# esp32s3_min_system.net
KiCad netlist of a schematic drawn in EasyEDA Pro
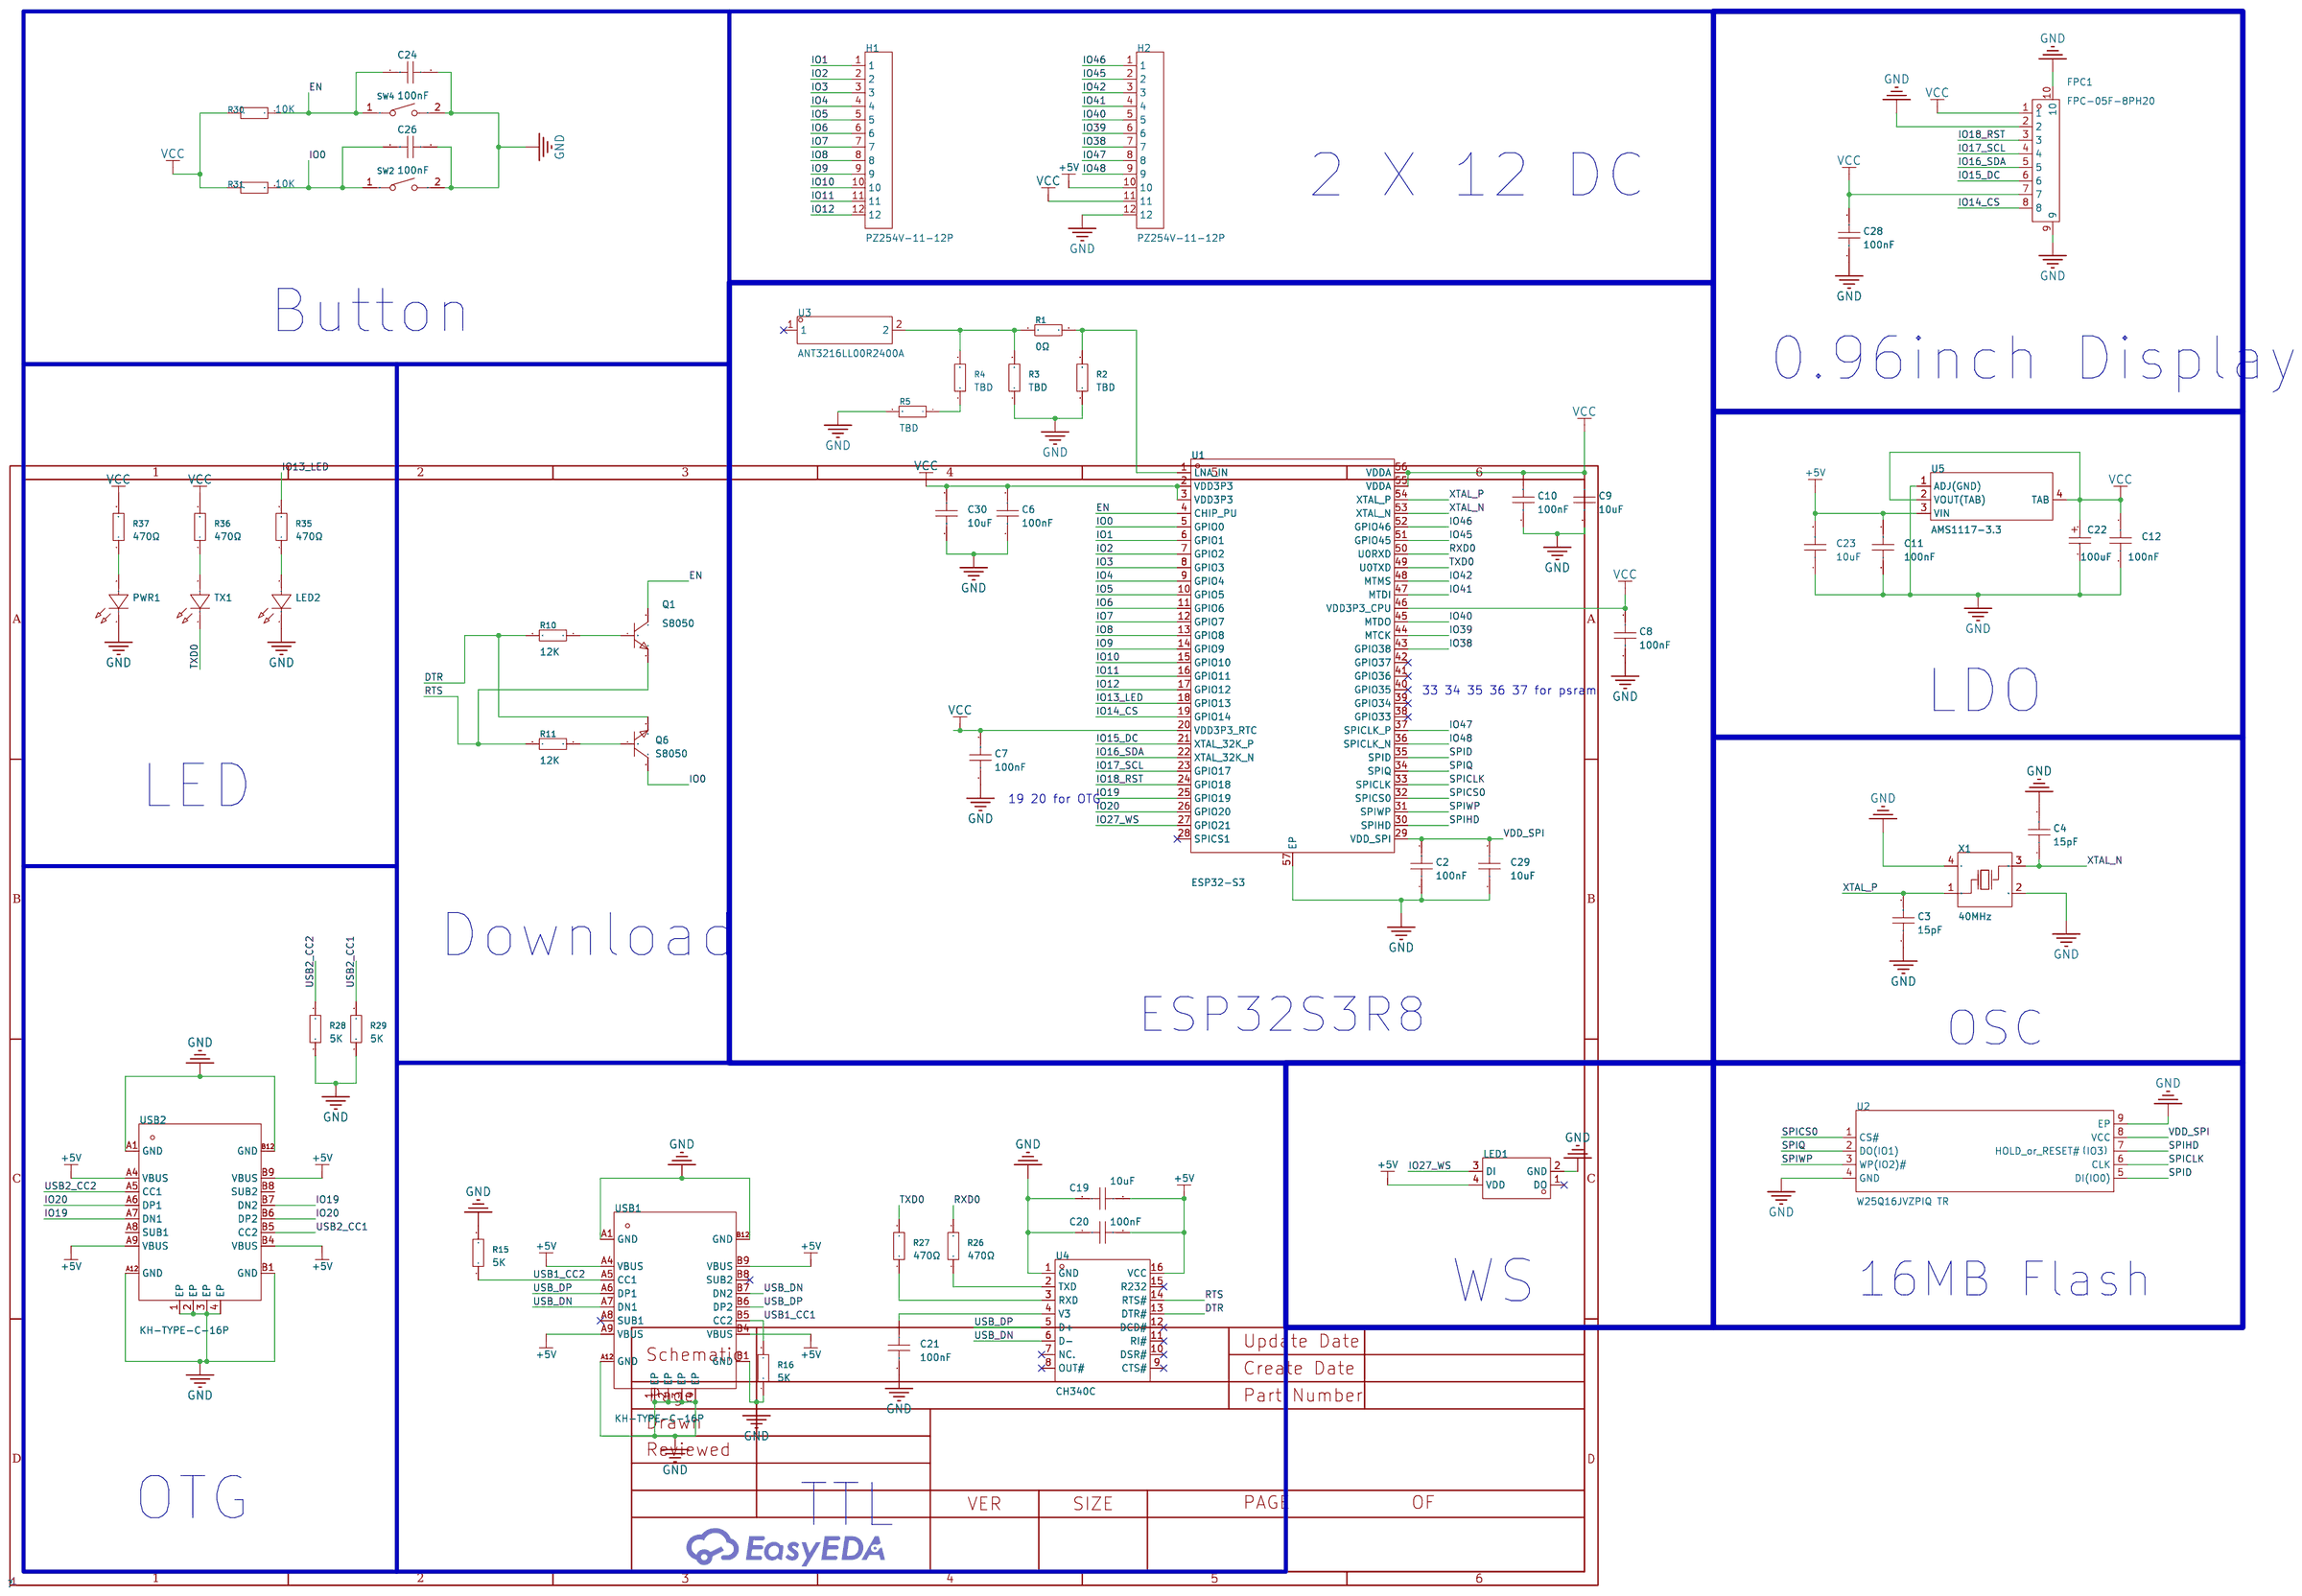
[diagram p0: schematic sheet]

(export (version "E")
  (design (tool "Eeschema 10.0.6"))
  (components
    (comp (ref "C2")
      (value "100nF")
      (footprint "easyedapro:C0402")
      (fields
        (field (name "Manufacturer Part") "CL05A105KA5NQNC")
        (field (name "Manufacturer") "SAMSUNG(三星)")
      )
      (libsource (lib "easyedapro") (part "CL05A105KA5NQNC"))
    )
    (comp (ref "C3")
      (value "15pF")
      (footprint "easyedapro:C0402")
      (fields
        (field (name "Manufacturer Part") "CL05A105KA5NQNC")
        (field (name "Manufacturer") "SAMSUNG(三星)")
      )
      (libsource (lib "easyedapro") (part "CL05A105KA5NQNC"))
    )
    (comp (ref "C4")
      (value "15pF")
      (footprint "easyedapro:C0402")
      (fields
        (field (name "Manufacturer Part") "CL05A105KA5NQNC")
        (field (name "Manufacturer") "SAMSUNG(三星)")
      )
      (libsource (lib "easyedapro") (part "CL05A105KA5NQNC"))
    )
    (comp (ref "C6")
      (value "100nF")
      (footprint "easyedapro:C0402")
      (fields
        (field (name "Manufacturer Part") "CL05A105KA5NQNC")
        (field (name "Manufacturer") "SAMSUNG(三星)")
      )
      (libsource (lib "easyedapro") (part "CL05A105KA5NQNC"))
    )
    (comp (ref "C7")
      (value "100nF")
      (footprint "easyedapro:C0402")
      (fields
        (field (name "Manufacturer Part") "CL05A105KA5NQNC")
        (field (name "Manufacturer") "SAMSUNG(三星)")
      )
      (libsource (lib "easyedapro") (part "CL05A105KA5NQNC"))
    )
    (comp (ref "C8")
      (value "100nF")
      (footprint "easyedapro:C0402")
      (fields
        (field (name "Manufacturer Part") "CL05A105KA5NQNC")
        (field (name "Manufacturer") "SAMSUNG(三星)")
      )
      (libsource (lib "easyedapro") (part "CL05A105KA5NQNC"))
    )
    (comp (ref "C9")
      (value "10uF")
      (footprint "easyedapro:C0402")
      (fields
        (field (name "Manufacturer Part") "CL05A105KA5NQNC")
        (field (name "Manufacturer") "SAMSUNG(三星)")
      )
      (libsource (lib "easyedapro") (part "CL05A105KA5NQNC"))
    )
    (comp (ref "C10")
      (value "100nF")
      (footprint "easyedapro:C0402")
      (fields
        (field (name "Manufacturer Part") "CL05A105KA5NQNC")
        (field (name "Manufacturer") "SAMSUNG(三星)")
      )
      (libsource (lib "easyedapro") (part "CL05A105KA5NQNC"))
    )
    (comp (ref "C11")
      (value "100nF")
      (footprint "easyedapro:C0402")
      (fields
        (field (name "Manufacturer Part") "CL05B104KO5NNNC")
        (field (name "Manufacturer") "SAMSUNG(三星)")
      )
      (libsource (lib "easyedapro") (part "CL05B104KO5NNNC"))
    )
    (comp (ref "C12")
      (value "100nF")
      (footprint "easyedapro:C0402")
      (fields
        (field (name "Manufacturer Part") "CL05B104KO5NNNC")
        (field (name "Manufacturer") "SAMSUNG(三星)")
      )
      (libsource (lib "easyedapro") (part "CL05B104KO5NNNC"))
    )
    (comp (ref "C19")
      (value "10uF")
      (footprint "easyedapro:C0603")
      (description "Capacitance:10uF Tolerance:±10% Tolerance:±10% Voltage Rating:10V Temperature Coefficient:X5R")
      (fields
        (field (name "Manufacturer Part") "CGA0603X5R106K100JT")
        (field (name "Manufacturer") "HRE(芯声)")
      )
      (libsource (lib "easyedapro") (part "CGA0603X5R106K100JT"))
    )
    (comp (ref "C20")
      (value "100nF")
      (footprint "easyedapro:C0402")
      (fields
        (field (name "Manufacturer Part") "CL05B104KO5NNNC")
        (field (name "Manufacturer") "SAMSUNG(三星)")
      )
      (libsource (lib "easyedapro") (part "CL05B104KO5NNNC"))
    )
    (comp (ref "C21")
      (value "100nF")
      (footprint "easyedapro:C0402")
      (fields
        (field (name "Manufacturer Part") "CL05B104KO5NNNC")
        (field (name "Manufacturer") "SAMSUNG(三星)")
      )
      (libsource (lib "easyedapro") (part "CL05B104KO5NNNC"))
    )
    (comp (ref "C22")
      (value "100uF")
      (footprint "easyedapro:CASE-B_3528")
      (fields (field (name "Manufacturer Part") "TAJB107K006RNJ") (field (name "Manufacturer") "Kyocera AVX"))
      (libsource (lib "easyedapro") (part "TAJB107K006RNJ"))
    )
    (comp (ref "C23")
      (value "10uF")
      (footprint "easyedapro:C0603")
      (description "Capacitance:10uF Tolerance:±10% Tolerance:±10% Voltage Rating:10V Temperature Coefficient:X5R")
      (fields
        (field (name "Manufacturer Part") "CGA0603X5R106K100JT")
        (field (name "Manufacturer") "HRE(芯声)")
      )
      (libsource (lib "easyedapro") (part "CGA0603X5R106K100JT"))
    )
    (comp (ref "C24")
      (value "100nF")
      (footprint "easyedapro:C0402")
      (fields
        (field (name "Manufacturer Part") "CL05B104KO5NNNC")
        (field (name "Manufacturer") "SAMSUNG(三星)")
      )
      (libsource (lib "easyedapro") (part "CL05B104KO5NNNC"))
    )
    (comp (ref "C26")
      (value "100nF")
      (footprint "easyedapro:C0402")
      (fields
        (field (name "Manufacturer Part") "CL05B104KO5NNNC")
        (field (name "Manufacturer") "SAMSUNG(三星)")
      )
      (libsource (lib "easyedapro") (part "CL05B104KO5NNNC"))
    )
    (comp (ref "C28")
      (value "100nF")
      (footprint "easyedapro:C0402")
      (fields
        (field (name "Manufacturer Part") "CL05A105KA5NQNC")
        (field (name "Manufacturer") "SAMSUNG(三星)")
      )
      (libsource (lib "easyedapro") (part "CL05A105KA5NQNC"))
    )
    (comp (ref "C29")
      (value "10uF")
      (footprint "easyedapro:C0603")
      (description "Capacitance:10uF Tolerance:±10% Tolerance:±10% Voltage Rating:10V Temperature Coefficient:X5R")
      (fields
        (field (name "Manufacturer Part") "CGA0603X5R106K100JT")
        (field (name "Manufacturer") "HRE(芯声)")
      )
      (libsource (lib "easyedapro") (part "CGA0603X5R106K100JT"))
    )
    (comp (ref "C30")
      (value "10uF")
      (footprint "easyedapro:C0603")
      (description "Capacitance:10uF Tolerance:±10% Tolerance:±10% Voltage Rating:10V Temperature Coefficient:X5R")
      (fields
        (field (name "Manufacturer Part") "CGA0603X5R106K100JT")
        (field (name "Manufacturer") "HRE(芯声)")
      )
      (libsource (lib "easyedapro") (part "CGA0603X5R106K100JT"))
    )
    (comp (ref "FPC1")
      (value "FPC-05F-8PH20")
      (footprint "easyedapro:FPC-SMD_8P-P0.50_FPC-05F-8PH20")
      (fields (field (name "Manufacturer") "XUNPU(讯普)"))
      (libsource (lib "easyedapro") (part "FPC-05F-8PH20"))
    )
    (comp (ref "H1")
      (value "PZ254V-11-12P")
      (footprint "easyedapro:HDR-TH_12P-P2.54-V-M")
      (fields (field (name "Manufacturer") "XFCN(兴飞)"))
      (libsource (lib "easyedapro") (part "PZ254V-11-12P"))
    )
    (comp (ref "H2")
      (value "PZ254V-11-12P")
      (footprint "easyedapro:HDR-TH_12P-P2.54-V-M")
      (fields (field (name "Manufacturer") "XFCN(兴飞)"))
      (libsource (lib "easyedapro") (part "PZ254V-11-12P"))
    )
    (comp (ref "LED1")
      (value "XL-2020RGBC-WS2812B")
      (footprint "easyedapro:LED-SMD_4P-L2.0-W2.0-BR-1")
      (fields (field (name "Manufacturer") "XINGLIGHT(成兴光)"))
      (libsource (lib "easyedapro") (part "XL-2020RGBC-WS2812B"))
    )
    (comp (ref "LED2")
      (value "XL-1608SURC-06")
      (footprint "easyedapro:LED0603-RD_RED")
      (fields (field (name "Manufacturer") "XINGLIGHT(成兴光)"))
      (libsource (lib "easyedapro") (part "XL-1608SURC-06"))
    )
    (comp (ref "PWR1")
      (value "XL-1608SURC-06")
      (footprint "easyedapro:LED0603-RD_RED")
      (fields (field (name "Manufacturer") "XINGLIGHT(成兴光)"))
      (libsource (lib "easyedapro") (part "XL-1608SURC-06"))
    )
    (comp (ref "Q1")
      (value "S8050")
      (footprint "easyedapro:SOT-23-3_L2.9-W1.3-P1.90-LS2.3-BR")
      (fields (field (name "Manufacturer") "宏嘉诚"))
      (libsource (lib "easyedapro") (part "S8050_C20069125"))
    )
    (comp (ref "Q6")
      (value "S8050")
      (footprint "easyedapro:SOT-23-3_L2.9-W1.3-P1.90-LS2.3-BR")
      (fields (field (name "Manufacturer") "宏嘉诚"))
      (libsource (lib "easyedapro") (part "S8050_C20069125"))
    )
    (comp (ref "R1")
      (value "0Ω")
      (footprint "easyedapro:R0402")
      (fields
        (field (name "Manufacturer Part") "0402WGF0000TCE")
        (field (name "Manufacturer") "UNI-ROYAL(厚声)")
      )
      (libsource (lib "easyedapro") (part "0402WGF0000TCE"))
    )
    (comp (ref "R2")
      (value "TBD")
      (footprint "easyedapro:R0402")
      (fields
        (field (name "Manufacturer Part") "0402WGF0000TCE")
        (field (name "Manufacturer") "UNI-ROYAL(厚声)")
      )
      (libsource (lib "easyedapro") (part "0402WGF0000TCE"))
    )
    (comp (ref "R3")
      (value "TBD")
      (footprint "easyedapro:R0402")
      (fields
        (field (name "Manufacturer Part") "0402WGF0000TCE")
        (field (name "Manufacturer") "UNI-ROYAL(厚声)")
      )
      (libsource (lib "easyedapro") (part "0402WGF0000TCE"))
    )
    (comp (ref "R4")
      (value "TBD")
      (footprint "easyedapro:R0402")
      (fields
        (field (name "Manufacturer Part") "0402WGF0000TCE")
        (field (name "Manufacturer") "UNI-ROYAL(厚声)")
      )
      (libsource (lib "easyedapro") (part "0402WGF0000TCE"))
    )
    (comp (ref "R5")
      (value "TBD")
      (footprint "easyedapro:R0402")
      (fields
        (field (name "Manufacturer Part") "0402WGF0000TCE")
        (field (name "Manufacturer") "UNI-ROYAL(厚声)")
      )
      (libsource (lib "easyedapro") (part "0402WGF0000TCE"))
    )
    (comp (ref "R10")
      (value "12K")
      (footprint "easyedapro:R0402")
      (fields
        (field (name "Manufacturer Part") "0402WGF4700TCE")
        (field (name "Manufacturer") "UNI-ROYAL(厚声)")
      )
      (libsource (lib "easyedapro") (part "0402WGF4700TCE"))
    )
    (comp (ref "R11")
      (value "12K")
      (footprint "easyedapro:R0402")
      (fields
        (field (name "Manufacturer Part") "0402WGF4700TCE")
        (field (name "Manufacturer") "UNI-ROYAL(厚声)")
      )
      (libsource (lib "easyedapro") (part "0402WGF4700TCE"))
    )
    (comp (ref "R15")
      (value "5K")
      (footprint "easyedapro:R0402")
      (fields
        (field (name "Manufacturer Part") "0402WGF4700TCE")
        (field (name "Manufacturer") "UNI-ROYAL(厚声)")
      )
      (libsource (lib "easyedapro") (part "0402WGF4700TCE"))
    )
    (comp (ref "R16")
      (value "5K")
      (footprint "easyedapro:R0402")
      (fields
        (field (name "Manufacturer Part") "0402WGF4700TCE")
        (field (name "Manufacturer") "UNI-ROYAL(厚声)")
      )
      (libsource (lib "easyedapro") (part "0402WGF4700TCE"))
    )
    (comp (ref "R26")
      (value "470Ω")
      (footprint "easyedapro:R0402")
      (fields
        (field (name "Manufacturer Part") "0402WGF4700TCE")
        (field (name "Manufacturer") "UNI-ROYAL(厚声)")
      )
      (libsource (lib "easyedapro") (part "0402WGF4700TCE"))
    )
    (comp (ref "R27")
      (value "470Ω")
      (footprint "easyedapro:R0402")
      (fields
        (field (name "Manufacturer Part") "0402WGF4700TCE")
        (field (name "Manufacturer") "UNI-ROYAL(厚声)")
      )
      (libsource (lib "easyedapro") (part "0402WGF4700TCE"))
    )
    (comp (ref "R28")
      (value "5K")
      (footprint "easyedapro:R0402")
      (fields
        (field (name "Manufacturer Part") "0402WGF4700TCE")
        (field (name "Manufacturer") "UNI-ROYAL(厚声)")
      )
      (libsource (lib "easyedapro") (part "0402WGF4700TCE"))
    )
    (comp (ref "R29")
      (value "5K")
      (footprint "easyedapro:R0402")
      (fields
        (field (name "Manufacturer Part") "0402WGF4700TCE")
        (field (name "Manufacturer") "UNI-ROYAL(厚声)")
      )
      (libsource (lib "easyedapro") (part "0402WGF4700TCE"))
    )
    (comp (ref "R30")
      (value "10K")
      (footprint "easyedapro:R0402")
      (fields
        (field (name "Manufacturer Part") "0402WGF4700TCE")
        (field (name "Manufacturer") "UNI-ROYAL(厚声)")
      )
      (libsource (lib "easyedapro") (part "0402WGF4700TCE"))
    )
    (comp (ref "R31")
      (value "10K")
      (footprint "easyedapro:R0402")
      (fields
        (field (name "Manufacturer Part") "0402WGF4700TCE")
        (field (name "Manufacturer") "UNI-ROYAL(厚声)")
      )
      (libsource (lib "easyedapro") (part "0402WGF4700TCE"))
    )
    (comp (ref "R35")
      (value "470Ω")
      (footprint "easyedapro:R0402")
      (fields
        (field (name "Manufacturer Part") "0402WGF4700TCE")
        (field (name "Manufacturer") "UNI-ROYAL(厚声)")
      )
      (libsource (lib "easyedapro") (part "0402WGF4700TCE"))
    )
    (comp (ref "R36")
      (value "470Ω")
      (footprint "easyedapro:R0402")
      (fields
        (field (name "Manufacturer Part") "0402WGF4700TCE")
        (field (name "Manufacturer") "UNI-ROYAL(厚声)")
      )
      (libsource (lib "easyedapro") (part "0402WGF4700TCE"))
    )
    (comp (ref "R37")
      (value "470Ω")
      (footprint "easyedapro:R0402")
      (fields
        (field (name "Manufacturer Part") "0402WGF4700TCE")
        (field (name "Manufacturer") "UNI-ROYAL(厚声)")
      )
      (libsource (lib "easyedapro") (part "0402WGF4700TCE"))
    )
    (comp (ref "SW2")
      (value "TS-1088-AR02016")
      (footprint "easyedapro:SW-SMD_L3.9-W3.0-P4.45")
      (fields (field (name "Manufacturer") "XUNPU(讯普)"))
      (libsource (lib "easyedapro") (part "TS-1088-AR02016"))
    )
    (comp (ref "SW4")
      (value "TS-1088-AR02016")
      (footprint "easyedapro:SW-SMD_L3.9-W3.0-P4.45")
      (fields (field (name "Manufacturer") "XUNPU(讯普)"))
      (libsource (lib "easyedapro") (part "TS-1088-AR02016"))
    )
    (comp (ref "TX1")
      (value "XL-1608SURC-06")
      (footprint "easyedapro:LED0603-RD_RED")
      (fields (field (name "Manufacturer") "XINGLIGHT(成兴光)"))
      (libsource (lib "easyedapro") (part "XL-1608SURC-06"))
    )
    (comp (ref "U1")
      (value "ESP32-S3")
      (footprint "easyedapro:QFN-56_L7.0-W7.0-P0.40-TL-EP4.0")
      (fields (field (name "Manufacturer") "ESPRESSIF(乐鑫)"))
      (libsource (lib "easyedapro") (part "ESP32-S3"))
    )
    (comp (ref "U2")
      (value "W25Q16JVZPIQ TR")
      (footprint "easyedapro:WSON-8_L6.0-W5.0-P1.27-BL-EP")
      (fields (field (name "Manufacturer") "WINBOND(华邦)"))
      (libsource (lib "easyedapro") (part "W25Q16JVZPIQ TR"))
    )
    (comp (ref "U3")
      (value "ANT3216LL00R2400A")
      (footprint "easyedapro:ANT-SMD_L3.2-W1.6")
      (fields (field (name "Manufacturer") "YAGEO(国巨)"))
      (libsource (lib "easyedapro") (part "ANT3216LL00R2400A"))
    )
    (comp (ref "U4")
      (value "CH340C")
      (footprint "easyedapro:SOP-16_L10.0-W3.9-P1.27-LS6.0-BL")
      (fields (field (name "Manufacturer") "WCH(南京沁恒)"))
      (libsource (lib "easyedapro") (part "CH340C"))
    )
    (comp (ref "U5")
      (value "AMS1117-3.3")
      (footprint "easyedapro:SOT-223-4_L6.5-W3.5-P2.30-LS7.0-BR")
      (fields (field (name "Manufacturer") "UMW(友台半导体)"))
      (libsource (lib "easyedapro") (part "AMS1117-3.3_C347222"))
    )
    (comp (ref "USB1")
      (value "KH-TYPE-C-16P")
      (footprint "easyedapro:USB-C-SMD_KH-TYPE-C-16P")
      (fields (field (name "Manufacturer") "kinghelm(金航标)"))
      (libsource (lib "easyedapro") (part "KH-TYPE-C-16P"))
    )
    (comp (ref "USB2")
      (value "KH-TYPE-C-16P")
      (footprint "easyedapro:USB-C-SMD_KH-TYPE-C-16P")
      (fields (field (name "Manufacturer") "kinghelm(金航标)"))
      (libsource (lib "easyedapro") (part "KH-TYPE-C-16P"))
    )
    (comp (ref "X1")
      (value "40MHz")
      (footprint "easyedapro:OSC-SMD_4P-L3.2-W2.5-BL_SIT8008BI")
      (fields (field (name "Manufacturer Part") "X322540MPB4SI") (field (name "Manufacturer") "YXC(扬兴晶振)"))
      (libsource (lib "easyedapro") (part "X322540MPB4SI"))
    )
  )
  (nets
    (net (code "1") (name "+5V") (class "Default")
      (node (ref "C11") (pin "1") (pinfunction "1_1") (pintype "unspecified"))
      (node (ref "C19") (pin "1") (pinfunction "1_1") (pintype "unspecified"))
      (node (ref "C20") (pin "2") (pinfunction "2_2") (pintype "unspecified"))
      (node (ref "C23") (pin "2") (pinfunction "2_2") (pintype "unspecified"))
      (node (ref "H2") (pin "10") (pinfunction "10_10") (pintype "unspecified"))
      (node (ref "LED1") (pin "4") (pinfunction "VDD_4") (pintype "unspecified"))
      (node (ref "U4") (pin "16") (pinfunction "VCC_16") (pintype "unspecified"))
      (node (ref "U5") (pin "3") (pinfunction "VIN_3") (pintype "unspecified"))
      (node (ref "USB1") (pin "A4") (pinfunction "VBUS_A4") (pintype "unspecified"))
      (node (ref "USB1") (pin "A9") (pinfunction "VBUS_A9") (pintype "unspecified"))
      (node (ref "USB1") (pin "B4") (pinfunction "VBUS_B4") (pintype "unspecified"))
      (node (ref "USB1") (pin "B9") (pinfunction "VBUS_B9") (pintype "unspecified"))
      (node (ref "USB2") (pin "A4") (pinfunction "VBUS_A4") (pintype "unspecified"))
      (node (ref "USB2") (pin "A9") (pinfunction "VBUS_A9") (pintype "unspecified"))
      (node (ref "USB2") (pin "B4") (pinfunction "VBUS_B4") (pintype "unspecified"))
      (node (ref "USB2") (pin "B9") (pinfunction "VBUS_B9") (pintype "unspecified"))
    )
    (net (code "2") (name "/DTR") (class "Default")
      (node (ref "Q6") (pin "2") (pinfunction "E_2") (pintype "input"))
      (node (ref "R10") (pin "2") (pinfunction "2_2") (pintype "input"))
      (node (ref "U4") (pin "13") (pinfunction "DTR#_13") (pintype "unspecified"))
    )
    (net (code "3") (name "/EN") (class "Default")
      (node (ref "C24") (pin "1") (pinfunction "1_1") (pintype "unspecified"))
      (node (ref "Q1") (pin "3") (pinfunction "C_3") (pintype "input"))
      (node (ref "R30") (pin "1") (pinfunction "1_1") (pintype "input"))
      (node (ref "SW4") (pin "1") (pinfunction "1_1") (pintype "input"))
      (node (ref "U1") (pin "4") (pinfunction "CHIP_PU_4") (pintype "unspecified"))
    )
    (net (code "4") (name "/IO0") (class "Default")
      (node (ref "C26") (pin "2") (pinfunction "2_2") (pintype "unspecified"))
      (node (ref "Q6") (pin "3") (pinfunction "C_3") (pintype "input"))
      (node (ref "R31") (pin "1") (pinfunction "1_1") (pintype "input"))
      (node (ref "SW2") (pin "1") (pinfunction "1_1") (pintype "input"))
      (node (ref "U1") (pin "5") (pinfunction "GPIO0_5") (pintype "unspecified"))
    )
    (net (code "5") (name "/IO1") (class "Default")
      (node (ref "H1") (pin "1") (pinfunction "1_1") (pintype "unspecified"))
      (node (ref "U1") (pin "6") (pinfunction "GPIO1_6") (pintype "unspecified"))
    )
    (net (code "6") (name "/IO2") (class "Default")
      (node (ref "H1") (pin "2") (pinfunction "2_2") (pintype "unspecified"))
      (node (ref "U1") (pin "7") (pinfunction "GPIO2_7") (pintype "unspecified"))
    )
    (net (code "7") (name "/IO3") (class "Default")
      (node (ref "H1") (pin "3") (pinfunction "3_3") (pintype "unspecified"))
      (node (ref "U1") (pin "8") (pinfunction "GPIO3_8") (pintype "unspecified"))
    )
    (net (code "8") (name "/IO4") (class "Default")
      (node (ref "H1") (pin "4") (pinfunction "4_4") (pintype "unspecified"))
      (node (ref "U1") (pin "9") (pinfunction "GPIO4_9") (pintype "unspecified"))
    )
    (net (code "9") (name "/IO5") (class "Default")
      (node (ref "H1") (pin "5") (pinfunction "5_5") (pintype "unspecified"))
      (node (ref "U1") (pin "10") (pinfunction "GPIO5_10") (pintype "unspecified"))
    )
    (net (code "10") (name "/IO6") (class "Default")
      (node (ref "H1") (pin "6") (pinfunction "6_6") (pintype "unspecified"))
      (node (ref "U1") (pin "11") (pinfunction "GPIO6_11") (pintype "unspecified"))
    )
    (net (code "11") (name "/IO7") (class "Default")
      (node (ref "H1") (pin "7") (pinfunction "7_7") (pintype "unspecified"))
      (node (ref "U1") (pin "12") (pinfunction "GPIO7_12") (pintype "unspecified"))
    )
    (net (code "12") (name "/IO8") (class "Default")
      (node (ref "H1") (pin "8") (pinfunction "8_8") (pintype "unspecified"))
      (node (ref "U1") (pin "13") (pinfunction "GPIO8_13") (pintype "unspecified"))
    )
    (net (code "13") (name "/IO9") (class "Default")
      (node (ref "H1") (pin "9") (pinfunction "9_9") (pintype "unspecified"))
      (node (ref "U1") (pin "14") (pinfunction "GPIO9_14") (pintype "unspecified"))
    )
    (net (code "14") (name "/IO10") (class "Default")
      (node (ref "H1") (pin "10") (pinfunction "10_10") (pintype "unspecified"))
      (node (ref "U1") (pin "15") (pinfunction "GPIO10_15") (pintype "unspecified"))
    )
    (net (code "15") (name "/IO11") (class "Default")
      (node (ref "H1") (pin "11") (pinfunction "11_11") (pintype "unspecified"))
      (node (ref "U1") (pin "16") (pinfunction "GPIO11_16") (pintype "unspecified"))
    )
    (net (code "16") (name "/IO12") (class "Default")
      (node (ref "H1") (pin "12") (pinfunction "12_12") (pintype "unspecified"))
      (node (ref "U1") (pin "17") (pinfunction "GPIO12_17") (pintype "unspecified"))
    )
    (net (code "17") (name "/IO13_LED") (class "Default")
      (node (ref "R35") (pin "2") (pinfunction "2_2") (pintype "input"))
      (node (ref "U1") (pin "18") (pinfunction "GPIO13_18") (pintype "unspecified"))
    )
    (net (code "18") (name "/IO14_CS") (class "Default")
      (node (ref "FPC1") (pin "8") (pinfunction "8_8") (pintype "unspecified"))
      (node (ref "U1") (pin "19") (pinfunction "GPIO14_19") (pintype "unspecified"))
    )
    (net (code "19") (name "/IO15_DC") (class "Default")
      (node (ref "FPC1") (pin "6") (pinfunction "6_6") (pintype "unspecified"))
      (node (ref "U1") (pin "21") (pinfunction "XTAL_32K_P_21") (pintype "unspecified"))
    )
    (net (code "20") (name "/IO16_SDA") (class "Default")
      (node (ref "FPC1") (pin "5") (pinfunction "5_5") (pintype "unspecified"))
      (node (ref "U1") (pin "22") (pinfunction "XTAL_32K_N_22") (pintype "unspecified"))
    )
    (net (code "21") (name "/IO17_SCL") (class "Default")
      (node (ref "FPC1") (pin "4") (pinfunction "4_4") (pintype "unspecified"))
      (node (ref "U1") (pin "23") (pinfunction "GPIO17_23") (pintype "unspecified"))
    )
    (net (code "22") (name "/IO18_RST") (class "Default")
      (node (ref "FPC1") (pin "3") (pinfunction "3_3") (pintype "unspecified"))
      (node (ref "U1") (pin "24") (pinfunction "GPIO18_24") (pintype "unspecified"))
    )
    (net (code "23") (name "/IO19") (class "Default")
      (node (ref "U1") (pin "25") (pinfunction "GPIO19_25") (pintype "unspecified"))
      (node (ref "USB2") (pin "A7") (pinfunction "DN1_A7") (pintype "unspecified"))
      (node (ref "USB2") (pin "B7") (pinfunction "DN2_B7") (pintype "unspecified"))
    )
    (net (code "24") (name "/IO20") (class "Default")
      (node (ref "U1") (pin "26") (pinfunction "GPIO20_26") (pintype "unspecified"))
      (node (ref "USB2") (pin "A6") (pinfunction "DP1_A6") (pintype "unspecified"))
      (node (ref "USB2") (pin "B6") (pinfunction "DP2_B6") (pintype "unspecified"))
    )
    (net (code "25") (name "/IO27_WS") (class "Default")
      (node (ref "LED1") (pin "3") (pinfunction "DI_3") (pintype "unspecified"))
      (node (ref "U1") (pin "27") (pinfunction "GPIO21_27") (pintype "unspecified"))
    )
    (net (code "26") (name "/IO38") (class "Default")
      (node (ref "H2") (pin "7") (pinfunction "7_7") (pintype "unspecified"))
      (node (ref "U1") (pin "43") (pinfunction "GPIO38_43") (pintype "unspecified"))
    )
    (net (code "27") (name "/IO39") (class "Default")
      (node (ref "H2") (pin "6") (pinfunction "6_6") (pintype "unspecified"))
      (node (ref "U1") (pin "44") (pinfunction "MTCK_44") (pintype "unspecified"))
    )
    (net (code "28") (name "/IO40") (class "Default")
      (node (ref "H2") (pin "5") (pinfunction "5_5") (pintype "unspecified"))
      (node (ref "U1") (pin "45") (pinfunction "MTDO_45") (pintype "unspecified"))
    )
    (net (code "29") (name "/IO41") (class "Default")
      (node (ref "H2") (pin "4") (pinfunction "4_4") (pintype "unspecified"))
      (node (ref "U1") (pin "47") (pinfunction "MTDI_47") (pintype "unspecified"))
    )
    (net (code "30") (name "/IO42") (class "Default")
      (node (ref "H2") (pin "3") (pinfunction "3_3") (pintype "unspecified"))
      (node (ref "U1") (pin "48") (pinfunction "MTMS_48") (pintype "unspecified"))
    )
    (net (code "31") (name "/IO45") (class "Default")
      (node (ref "H2") (pin "2") (pinfunction "2_2") (pintype "unspecified"))
      (node (ref "U1") (pin "51") (pinfunction "GPIO45_51") (pintype "unspecified"))
    )
    (net (code "32") (name "/IO46") (class "Default")
      (node (ref "H2") (pin "1") (pinfunction "1_1") (pintype "unspecified"))
      (node (ref "U1") (pin "52") (pinfunction "GPIO46_52") (pintype "unspecified"))
    )
    (net (code "33") (name "/IO47") (class "Default")
      (node (ref "H2") (pin "8") (pinfunction "8_8") (pintype "unspecified"))
      (node (ref "U1") (pin "37") (pinfunction "SPICLK_P_37") (pintype "unspecified"))
    )
    (net (code "34") (name "/IO48") (class "Default")
      (node (ref "H2") (pin "9") (pinfunction "9_9") (pintype "unspecified"))
      (node (ref "U1") (pin "36") (pinfunction "SPICLK_N_36") (pintype "unspecified"))
    )
    (net (code "35") (name "/RTS") (class "Default")
      (node (ref "Q1") (pin "2") (pinfunction "E_2") (pintype "input"))
      (node (ref "R11") (pin "2") (pinfunction "2_2") (pintype "input"))
      (node (ref "U4") (pin "14") (pinfunction "RTS#_14") (pintype "unspecified"))
    )
    (net (code "36") (name "/RXD0") (class "Default")
      (node (ref "R26") (pin "2") (pinfunction "2_2") (pintype "input"))
      (node (ref "U1") (pin "50") (pinfunction "U0RXD_50") (pintype "unspecified"))
    )
    (net (code "37") (name "/SPICLK") (class "Default")
      (node (ref "U1") (pin "33") (pinfunction "SPICLK_33") (pintype "unspecified"))
      (node (ref "U2") (pin "6") (pinfunction "CLK_6") (pintype "unspecified"))
    )
    (net (code "38") (name "/SPICS0") (class "Default")
      (node (ref "U1") (pin "32") (pinfunction "SPICS0_32") (pintype "unspecified"))
      (node (ref "U2") (pin "1") (pinfunction "CS#_1") (pintype "unspecified"))
    )
    (net (code "39") (name "/SPID") (class "Default")
      (node (ref "U1") (pin "35") (pinfunction "SPID_35") (pintype "unspecified"))
      (node (ref "U2") (pin "5") (pinfunction "DI(IO0)_5") (pintype "unspecified"))
    )
    (net (code "40") (name "/SPIHD") (class "Default")
      (node (ref "U1") (pin "30") (pinfunction "SPIHD_30") (pintype "unspecified"))
      (node (ref "U2") (pin "7") (pinfunction "HOLD_or_RESET#（IO3）_7") (pintype "unspecified"))
    )
    (net (code "41") (name "/SPIQ") (class "Default")
      (node (ref "U1") (pin "34") (pinfunction "SPIQ_34") (pintype "unspecified"))
      (node (ref "U2") (pin "2") (pinfunction "DO(IO1)_2") (pintype "unspecified"))
    )
    (net (code "42") (name "/SPIWP") (class "Default")
      (node (ref "U1") (pin "31") (pinfunction "SPIWP_31") (pintype "unspecified"))
      (node (ref "U2") (pin "3") (pinfunction "WP(IO2)#_3") (pintype "unspecified"))
    )
    (net (code "43") (name "/TXD0") (class "Default")
      (node (ref "R27") (pin "2") (pinfunction "2_2") (pintype "input"))
      (node (ref "TX1") (pin "1") (pinfunction "K_1") (pintype "unspecified"))
      (node (ref "U1") (pin "49") (pinfunction "U0TXD_49") (pintype "unspecified"))
    )
    (net (code "44") (name "/USB1_CC1") (class "Default")
      (node (ref "R16") (pin "2") (pinfunction "2_2") (pintype "input"))
      (node (ref "USB1") (pin "B5") (pinfunction "CC2_B5") (pintype "unspecified"))
    )
    (net (code "45") (name "/USB1_CC2") (class "Default")
      (node (ref "R15") (pin "1") (pinfunction "1_1") (pintype "input"))
      (node (ref "USB1") (pin "A5") (pinfunction "CC1_A5") (pintype "unspecified"))
    )
    (net (code "46") (name "/USB2_CC1") (class "Default")
      (node (ref "R29") (pin "2") (pinfunction "2_2") (pintype "input"))
      (node (ref "USB2") (pin "B5") (pinfunction "CC2_B5") (pintype "unspecified"))
    )
    (net (code "47") (name "/USB2_CC2") (class "Default")
      (node (ref "R28") (pin "2") (pinfunction "2_2") (pintype "input"))
      (node (ref "USB2") (pin "A5") (pinfunction "CC1_A5") (pintype "unspecified"))
    )
    (net (code "48") (name "/USB_DN") (class "Default")
      (node (ref "U4") (pin "6") (pinfunction "D-_6") (pintype "unspecified"))
      (node (ref "USB1") (pin "A7") (pinfunction "DN1_A7") (pintype "unspecified"))
      (node (ref "USB1") (pin "B7") (pinfunction "DN2_B7") (pintype "unspecified"))
    )
    (net (code "49") (name "/USB_DP") (class "Default")
      (node (ref "U4") (pin "5") (pinfunction "D+_5") (pintype "unspecified"))
      (node (ref "USB1") (pin "A6") (pinfunction "DP1_A6") (pintype "unspecified"))
      (node (ref "USB1") (pin "B6") (pinfunction "DP2_B6") (pintype "unspecified"))
    )
    (net (code "50") (name "/VDD_SPI") (class "Default")
      (node (ref "C2") (pin "2") (pinfunction "2_2") (pintype "unspecified"))
      (node (ref "C29") (pin "2") (pinfunction "2_2") (pintype "unspecified"))
      (node (ref "U1") (pin "29") (pinfunction "VDD_SPI_29") (pintype "unspecified"))
      (node (ref "U2") (pin "8") (pinfunction "VCC_8") (pintype "unspecified"))
    )
    (net (code "51") (name "/XTAL_N") (class "Default")
      (node (ref "C4") (pin "1") (pinfunction "1_1") (pintype "unspecified"))
      (node (ref "U1") (pin "53") (pinfunction "XTAL_N_53") (pintype "unspecified"))
      (node (ref "X1") (pin "3") (pinfunction "OSC2_3") (pintype "unspecified"))
    )
    (net (code "52") (name "/XTAL_P") (class "Default")
      (node (ref "C3") (pin "2") (pinfunction "2_2") (pintype "unspecified"))
      (node (ref "U1") (pin "54") (pinfunction "XTAL_P_54") (pintype "unspecified"))
      (node (ref "X1") (pin "1") (pinfunction "OSC1_1") (pintype "unspecified"))
    )
    (net (code "53") (name "GND") (class "Default")
      (node (ref "C10") (pin "1") (pinfunction "1_1") (pintype "unspecified"))
      (node (ref "C11") (pin "2") (pinfunction "2_2") (pintype "unspecified"))
      (node (ref "C12") (pin "2") (pinfunction "2_2") (pintype "unspecified"))
      (node (ref "C19") (pin "2") (pinfunction "2_2") (pintype "unspecified"))
      (node (ref "C2") (pin "1") (pinfunction "1_1") (pintype "unspecified"))
      (node (ref "C20") (pin "1") (pinfunction "1_1") (pintype "unspecified"))
      (node (ref "C21") (pin "1") (pinfunction "1_1") (pintype "unspecified"))
      (node (ref "C22") (pin "2") (pinfunction "2_2") (pintype "input"))
      (node (ref "C23") (pin "1") (pinfunction "1_1") (pintype "unspecified"))
      (node (ref "C24") (pin "2") (pinfunction "2_2") (pintype "unspecified"))
      (node (ref "C26") (pin "1") (pinfunction "1_1") (pintype "unspecified"))
      (node (ref "C28") (pin "1") (pinfunction "1_1") (pintype "unspecified"))
      (node (ref "C29") (pin "1") (pinfunction "1_1") (pintype "unspecified"))
      (node (ref "C3") (pin "1") (pinfunction "1_1") (pintype "unspecified"))
      (node (ref "C30") (pin "1") (pinfunction "1_1") (pintype "unspecified"))
      (node (ref "C4") (pin "2") (pinfunction "2_2") (pintype "unspecified"))
      (node (ref "C6") (pin "1") (pinfunction "1_1") (pintype "unspecified"))
      (node (ref "C7") (pin "1") (pinfunction "1_1") (pintype "unspecified"))
      (node (ref "C8") (pin "1") (pinfunction "1_1") (pintype "unspecified"))
      (node (ref "C9") (pin "1") (pinfunction "1_1") (pintype "unspecified"))
      (node (ref "FPC1") (pin "10") (pinfunction "10_10") (pintype "unspecified"))
      (node (ref "FPC1") (pin "2") (pinfunction "2_2") (pintype "unspecified"))
      (node (ref "FPC1") (pin "9") (pinfunction "9_9") (pintype "unspecified"))
      (node (ref "H2") (pin "12") (pinfunction "12_12") (pintype "unspecified"))
      (node (ref "LED1") (pin "2") (pinfunction "GND_2") (pintype "unspecified"))
      (node (ref "LED2") (pin "1") (pinfunction "K_1") (pintype "unspecified"))
      (node (ref "PWR1") (pin "1") (pinfunction "K_1") (pintype "unspecified"))
      (node (ref "R15") (pin "2") (pinfunction "2_2") (pintype "input"))
      (node (ref "R16") (pin "1") (pinfunction "1_1") (pintype "input"))
      (node (ref "R2") (pin "1") (pinfunction "1_1") (pintype "input"))
      (node (ref "R28") (pin "1") (pinfunction "1_1") (pintype "input"))
      (node (ref "R29") (pin "1") (pinfunction "1_1") (pintype "input"))
      (node (ref "R3") (pin "1") (pinfunction "1_1") (pintype "input"))
      (node (ref "R5") (pin "2") (pinfunction "2_2") (pintype "input"))
      (node (ref "SW2") (pin "2") (pinfunction "2_2") (pintype "input"))
      (node (ref "SW4") (pin "2") (pinfunction "2_2") (pintype "input"))
      (node (ref "U1") (pin "57") (pinfunction "EP_57") (pintype "unspecified"))
      (node (ref "U2") (pin "4") (pinfunction "GND_4") (pintype "unspecified"))
      (node (ref "U2") (pin "9") (pinfunction "EP_9") (pintype "unspecified"))
      (node (ref "U4") (pin "1") (pinfunction "GND_1") (pintype "unspecified"))
      (node (ref "U5") (pin "1") (pinfunction "ADJ(GND)_1") (pintype "unspecified"))
      (node (ref "USB1") (pin "1") (pinfunction "EP_1") (pintype "unspecified"))
      (node (ref "USB1") (pin "2") (pinfunction "EP_2") (pintype "unspecified"))
      (node (ref "USB1") (pin "3") (pinfunction "EP_3") (pintype "unspecified"))
      (node (ref "USB1") (pin "4") (pinfunction "EP_4") (pintype "unspecified"))
      (node (ref "USB1") (pin "A1") (pinfunction "GND_A1") (pintype "unspecified"))
      (node (ref "USB1") (pin "A12") (pinfunction "GND_A12") (pintype "unspecified"))
      (node (ref "USB1") (pin "B1") (pinfunction "GND_B1") (pintype "unspecified"))
      (node (ref "USB1") (pin "B12") (pinfunction "GND_B12") (pintype "unspecified"))
      (node (ref "USB2") (pin "1") (pinfunction "EP_1") (pintype "unspecified"))
      (node (ref "USB2") (pin "2") (pinfunction "EP_2") (pintype "unspecified"))
      (node (ref "USB2") (pin "3") (pinfunction "EP_3") (pintype "unspecified"))
      (node (ref "USB2") (pin "4") (pinfunction "EP_4") (pintype "unspecified"))
      (node (ref "USB2") (pin "A1") (pinfunction "GND_A1") (pintype "unspecified"))
      (node (ref "USB2") (pin "A12") (pinfunction "GND_A12") (pintype "unspecified"))
      (node (ref "USB2") (pin "B1") (pinfunction "GND_B1") (pintype "unspecified"))
      (node (ref "USB2") (pin "B12") (pinfunction "GND_B12") (pintype "unspecified"))
      (node (ref "X1") (pin "2") (pinfunction "GND_2") (pintype "unspecified"))
      (node (ref "X1") (pin "4") (pinfunction "GND_4") (pintype "unspecified"))
    )
    (net (code "54") (name "Net-(LED2-A)") (class "Default")
      (node (ref "LED2") (pin "2") (pinfunction "A_2") (pintype "unspecified"))
      (node (ref "R35") (pin "1") (pinfunction "1_1") (pintype "input"))
    )
    (net (code "55") (name "Net-(PWR1-A)") (class "Default")
      (node (ref "PWR1") (pin "2") (pinfunction "A_2") (pintype "unspecified"))
      (node (ref "R37") (pin "1") (pinfunction "1_1") (pintype "input"))
    )
    (net (code "56") (name "Net-(Q1-B)") (class "Default")
      (node (ref "Q1") (pin "1") (pinfunction "B_1") (pintype "input"))
      (node (ref "R10") (pin "1") (pinfunction "1_1") (pintype "input"))
    )
    (net (code "57") (name "Net-(Q6-B)") (class "Default")
      (node (ref "Q6") (pin "1") (pinfunction "B_1") (pintype "input"))
      (node (ref "R11") (pin "1") (pinfunction "1_1") (pintype "input"))
    )
    (net (code "58") (name "Net-(R1-Pad1)") (class "Default")
      (node (ref "R1") (pin "1") (pinfunction "1_1") (pintype "input"))
      (node (ref "R3") (pin "2") (pinfunction "2_2") (pintype "input"))
      (node (ref "R4") (pin "2") (pinfunction "2_2") (pintype "input"))
      (node (ref "U3") (pin "2") (pinfunction "2_2") (pintype "unspecified"))
    )
    (net (code "59") (name "Net-(R4-Pad1)") (class "Default")
      (node (ref "R4") (pin "1") (pinfunction "1_1") (pintype "input"))
      (node (ref "R5") (pin "1") (pinfunction "1_1") (pintype "input"))
    )
    (net (code "60") (name "Net-(TX1-A)") (class "Default")
      (node (ref "R36") (pin "1") (pinfunction "1_1") (pintype "input"))
      (node (ref "TX1") (pin "2") (pinfunction "A_2") (pintype "unspecified"))
    )
    (net (code "61") (name "Net-(U1-LNA_IN)") (class "Default")
      (node (ref "R1") (pin "2") (pinfunction "2_2") (pintype "input"))
      (node (ref "R2") (pin "2") (pinfunction "2_2") (pintype "input"))
      (node (ref "U1") (pin "1") (pinfunction "LNA_IN_1") (pintype "unspecified"))
    )
    (net (code "62") (name "Net-(U4-RXD)") (class "Default")
      (node (ref "R27") (pin "1") (pinfunction "1_1") (pintype "input"))
      (node (ref "U4") (pin "3") (pinfunction "RXD_3") (pintype "unspecified"))
    )
    (net (code "63") (name "Net-(U4-TXD)") (class "Default")
      (node (ref "R26") (pin "1") (pinfunction "1_1") (pintype "input"))
      (node (ref "U4") (pin "2") (pinfunction "TXD_2") (pintype "unspecified"))
    )
    (net (code "64") (name "Net-(U4-V3)") (class "Default")
      (node (ref "C21") (pin "2") (pinfunction "2_2") (pintype "unspecified"))
      (node (ref "U4") (pin "4") (pinfunction "V3_4") (pintype "unspecified"))
    )
    (net (code "65") (name "VCC") (class "Default")
      (node (ref "C10") (pin "2") (pinfunction "2_2") (pintype "unspecified"))
      (node (ref "C12") (pin "1") (pinfunction "1_1") (pintype "unspecified"))
      (node (ref "C22") (pin "1") (pinfunction "1_1") (pintype "input"))
      (node (ref "C28") (pin "2") (pinfunction "2_2") (pintype "unspecified"))
      (node (ref "C30") (pin "2") (pinfunction "2_2") (pintype "unspecified"))
      (node (ref "C6") (pin "2") (pinfunction "2_2") (pintype "unspecified"))
      (node (ref "C7") (pin "2") (pinfunction "2_2") (pintype "unspecified"))
      (node (ref "C8") (pin "2") (pinfunction "2_2") (pintype "unspecified"))
      (node (ref "C9") (pin "2") (pinfunction "2_2") (pintype "unspecified"))
      (node (ref "FPC1") (pin "1") (pinfunction "1_1") (pintype "unspecified"))
      (node (ref "FPC1") (pin "7") (pinfunction "7_7") (pintype "unspecified"))
      (node (ref "H2") (pin "11") (pinfunction "11_11") (pintype "unspecified"))
      (node (ref "R30") (pin "2") (pinfunction "2_2") (pintype "input"))
      (node (ref "R31") (pin "2") (pinfunction "2_2") (pintype "input"))
      (node (ref "R36") (pin "2") (pinfunction "2_2") (pintype "input"))
      (node (ref "R37") (pin "2") (pinfunction "2_2") (pintype "input"))
      (node (ref "U1") (pin "2") (pinfunction "VDD3P3_2") (pintype "unspecified"))
      (node (ref "U1") (pin "20") (pinfunction "VDD3P3_RTC_20") (pintype "unspecified"))
      (node (ref "U1") (pin "3") (pinfunction "VDD3P3_3") (pintype "unspecified"))
      (node (ref "U1") (pin "46") (pinfunction "VDD3P3_CPU_46") (pintype "unspecified"))
      (node (ref "U1") (pin "55") (pinfunction "VDDA_55") (pintype "unspecified"))
      (node (ref "U1") (pin "56") (pinfunction "VDDA_56") (pintype "unspecified"))
      (node (ref "U5") (pin "2") (pinfunction "VOUT(TAB)_2") (pintype "unspecified"))
      (node (ref "U5") (pin "4") (pinfunction "TAB_4") (pintype "unspecified"))
    )
    (net (code "66") (name "unconnected-(LED1-DO-Pad1)") (class "Default")
      (node (ref "LED1") (pin "1") (pinfunction "DO_1") (pintype "unspecified+no_connect"))
    )
    (net (code "67") (name "unconnected-(U1-GPIO33-Pad38)") (class "Default")
      (node (ref "U1") (pin "38") (pinfunction "GPIO33_38") (pintype "unspecified+no_connect"))
    )
    (net (code "68") (name "unconnected-(U1-GPIO34-Pad39)") (class "Default")
      (node (ref "U1") (pin "39") (pinfunction "GPIO34_39") (pintype "unspecified+no_connect"))
    )
    (net (code "69") (name "unconnected-(U1-GPIO35-Pad40)") (class "Default")
      (node (ref "U1") (pin "40") (pinfunction "GPIO35_40") (pintype "unspecified+no_connect"))
    )
    (net (code "70") (name "unconnected-(U1-GPIO36-Pad41)") (class "Default")
      (node (ref "U1") (pin "41") (pinfunction "GPIO36_41") (pintype "unspecified+no_connect"))
    )
    (net (code "71") (name "unconnected-(U1-GPIO37-Pad42)") (class "Default")
      (node (ref "U1") (pin "42") (pinfunction "GPIO37_42") (pintype "unspecified+no_connect"))
    )
    (net (code "72") (name "unconnected-(U1-SPICS1-Pad28)") (class "Default")
      (node (ref "U1") (pin "28") (pinfunction "SPICS1_28") (pintype "unspecified+no_connect"))
    )
    (net (code "73") (name "unconnected-(U3-Pad1)") (class "Default")
      (node (ref "U3") (pin "1") (pinfunction "1_1") (pintype "unspecified+no_connect"))
    )
    (net (code "74") (name "unconnected-(U4-CTS#-Pad9)") (class "Default")
      (node (ref "U4") (pin "9") (pinfunction "CTS#_9") (pintype "unspecified+no_connect"))
    )
    (net (code "75") (name "unconnected-(U4-DCD#-Pad12)") (class "Default")
      (node (ref "U4") (pin "12") (pinfunction "DCD#_12") (pintype "unspecified+no_connect"))
    )
    (net (code "76") (name "unconnected-(U4-DSR#-Pad10)") (class "Default")
      (node (ref "U4") (pin "10") (pinfunction "DSR#_10") (pintype "unspecified+no_connect"))
    )
    (net (code "77") (name "unconnected-(U4-NC.-Pad7)") (class "Default")
      (node (ref "U4") (pin "7") (pinfunction "NC._7") (pintype "unspecified+no_connect"))
    )
    (net (code "78") (name "unconnected-(U4-OUT#-Pad8)") (class "Default")
      (node (ref "U4") (pin "8") (pinfunction "OUT#_8") (pintype "unspecified+no_connect"))
    )
    (net (code "79") (name "unconnected-(U4-R232-Pad15)") (class "Default")
      (node (ref "U4") (pin "15") (pinfunction "R232_15") (pintype "unspecified+no_connect"))
    )
    (net (code "80") (name "unconnected-(U4-RI#-Pad11)") (class "Default")
      (node (ref "U4") (pin "11") (pinfunction "RI#_11") (pintype "unspecified+no_connect"))
    )
    (net (code "81") (name "unconnected-(USB1-SUB1-PadA8)") (class "Default")
      (node (ref "USB1") (pin "A8") (pinfunction "SUB1_A8") (pintype "unspecified+no_connect"))
    )
    (net (code "82") (name "unconnected-(USB1-SUB2-PadB8)") (class "Default")
      (node (ref "USB1") (pin "B8") (pinfunction "SUB2_B8") (pintype "unspecified+no_connect"))
    )
    (net (code "83") (name "unconnected-(USB2-SUB1-PadA8)") (class "Default")
      (node (ref "USB2") (pin "A8") (pinfunction "SUB1_A8") (pintype "unspecified"))
    )
    (net (code "84") (name "unconnected-(USB2-SUB2-PadB8)") (class "Default")
      (node (ref "USB2") (pin "B8") (pinfunction "SUB2_B8") (pintype "unspecified"))
    )
  )
)
